# schematic.net
KiCad netlist of a schematic drawn in Altium Designer
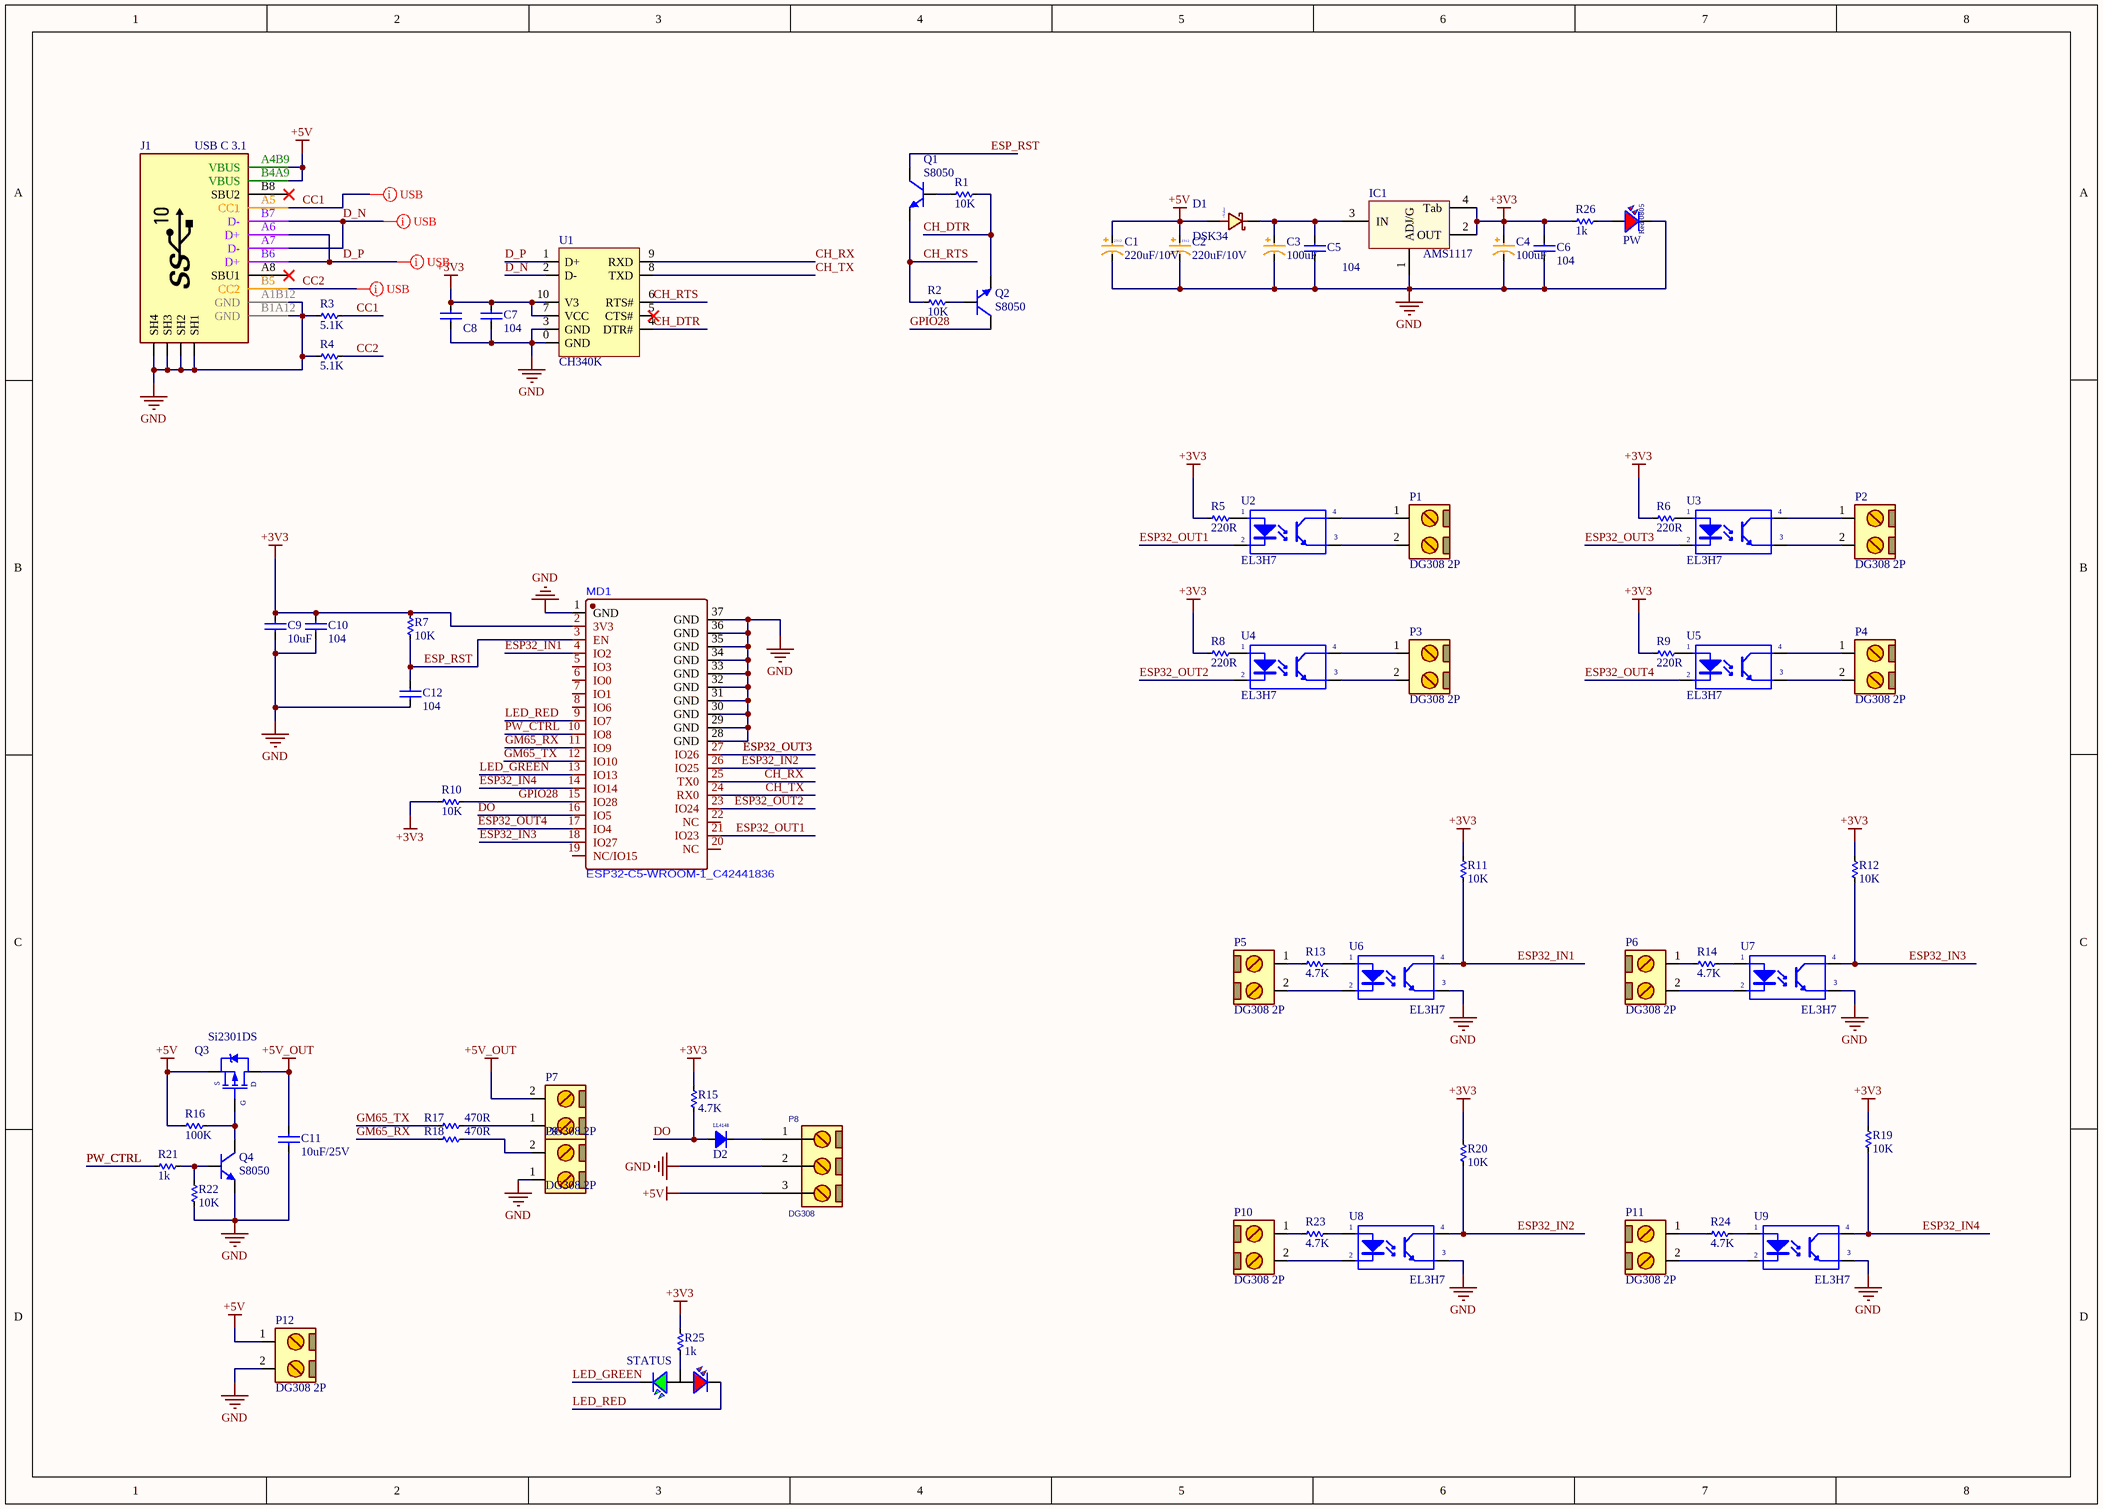
[diagram p0: schematic.SchDoc]

(export (version "E")
  (design (tool "Eeschema 10.0.6"))
  (components
    (comp (ref "C1")
      (value "220uF/10V")
      (footprint "C_tantalum_6032-2312")
      (description "Cap SMD 2312 (6032)")
      (libsource (lib "RD Integrated_Library") (part "Cap Tantalum 220uF 10V 2312"))
    )
    (comp (ref "C2")
      (value "220uF/10V")
      (footprint "C_tantalum_6032-2312")
      (description "Cap SMD 2312 (6032)")
      (libsource (lib "RD Integrated_Library") (part "Cap Tantalum 220uF 10V 2312"))
    )
    (comp (ref "C3")
      (value "100uF")
      (footprint "C_TANTALUM_3528_1210")
      (description "Cap Tantalum SMD 1210 (3528)")
      (fields (field (name "DESIGNED BY") "TranLuyen"))
      (libsource (lib "RD Integrated_Library") (part "Cap Tantalum 100uF 10V 1210 (3528)"))
    )
    (comp (ref "C4")
      (value "100uF")
      (footprint "C_TANTALUM_3528_1210")
      (description "Cap Tantalum SMD 1210 (3528)")
      (fields (field (name "DESIGNED BY") "TranLuyen"))
      (libsource (lib "RD Integrated_Library") (part "Cap Tantalum 100uF 10V 1210 (3528)"))
    )
    (comp (ref "C5")
      (value "104")
      (footprint "C_0805_SMD")
      (description "Cap SMD 0805 104-100nF-0.1uF 50V")
      (libsource (lib "RD Integrated_Library") (part "Cap 0805 104 100nF"))
    )
    (comp (ref "C6")
      (value "104")
      (footprint "C_0805_SMD")
      (description "Cap SMD 0805 104-100nF-0.1uF 50V")
      (libsource (lib "RD Integrated_Library") (part "Cap 0805 104 100nF"))
    )
    (comp (ref "C7")
      (value "104")
      (footprint "C_0805_SMD")
      (description "Cap SMD 0805 104-100nF-0.1uF 50V")
      (libsource (lib "RD Integrated_Library") (part "Cap 0805 104 100nF"))
    )
    (comp (ref "C8")
      (value "10uF/25V")
      (footprint "C_0805_SMD")
      (description "Cap SMD 0805 10uF")
      (libsource (lib "RD Integrated_Library") (part "Cap 0805 10uF 25V"))
    )
    (comp (ref "C9")
      (value "10uF")
      (footprint "C1206")
      (description "Cap SMD 1206 105-10uF 50V")
      (libsource (lib "RD Integrated_Library") (part "Cap 1206 10uF 50V"))
    )
    (comp (ref "C10")
      (value "104")
      (footprint "C_0805_SMD")
      (description "Cap SMD 0805 104-100nF-0.1uF 50V")
      (libsource (lib "RD Integrated_Library") (part "Cap 0805 104 100nF"))
    )
    (comp (ref "C11")
      (value "10uF/25V")
      (footprint "C_0805_SMD")
      (description "Cap SMD 0805 10uF")
      (libsource (lib "RD Integrated_Library") (part "Cap 0805 10uF 25V"))
    )
    (comp (ref "C12")
      (value "104")
      (footprint "C_0805_SMD")
      (description "Cap SMD 0805 104-100nF-0.1uF 50V")
      (libsource (lib "RD Integrated_Library") (part "Cap 0805 104 100nF"))
    )
    (comp (ref "D1")
      (value "DSK34")
      (footprint "D_SOD123W")
      (description "Surface-Mount Schottky Barrier Rectifier")
      (libsource (lib "RD Integrated_Library") (part "DSK34-SOD-123"))
    )
    (comp (ref "D2")
      (value "LL4148")
      (footprint "SOD80C_MFG")
      (description "0.2A, 100V, SOD80")
      (fields (field (name "DESIGNED BY") "Nhox"))
      (libsource (lib "RD Integrated_Library") (part "LL4148"))
    )
    (comp (ref "IC1")
      (value "AMS1117")
      (footprint "SOT223-4N")
      (description "SOT-223")
      (libsource (lib "RD Integrated_Library") (part "AMS1117-3.3V SOT223"))
    )
    (comp (ref "J1")
      (value "USB C 3.1")
      (footprint "USBC_SMD_16_USB4105 PAD L")
      (description "CONN, USB, Type C, USB 2.0, Right-Angle, SMD")
      (libsource (lib "RD Integrated_Library") (part "CONN_USBC_SMD_16_USB4105"))
    )
    (comp (ref "MD1")
      (value "ESP32-C5-WROOM-1_C42441836")
      (footprint "COMM-SMD_37P-P1.27-L27.5-W18.0-ESP32-C5-WROOM-1")
      (libsource (lib "CuongRD") (part "ESP32-C5-WROOM-1_C42441836"))
    )
    (comp (ref "P1")
      (value "DG308 2P")
      (footprint "DG308 KF120 2.54mm 2P - duplicate")
      (description "Header, 2-Pin, Medium DG308-KF120 2.54 2P 2.54mm")
      (fields (field (name "DESIGNED BY") "TranLuyen"))
      (libsource (lib "Schlib1") (part "DG308-KF120-2.54 2P-2.54mm"))
    )
    (comp (ref "P2")
      (value "DG308 2P")
      (footprint "DG308 KF120 2.54mm 2P - duplicate")
      (description "Header, 2-Pin, Medium DG308-KF120 2.54 2P 2.54mm")
      (fields (field (name "DESIGNED BY") "TranLuyen"))
      (libsource (lib "Schlib1") (part "DG308-KF120-2.54 2P-2.54mm"))
    )
    (comp (ref "P3")
      (value "DG308 2P")
      (footprint "DG308 KF120 2.54mm 2P - duplicate")
      (description "Header, 2-Pin, Medium DG308-KF120 2.54 2P 2.54mm")
      (fields (field (name "DESIGNED BY") "TranLuyen"))
      (libsource (lib "Schlib1") (part "DG308-KF120-2.54 2P-2.54mm"))
    )
    (comp (ref "P4")
      (value "DG308 2P")
      (footprint "DG308 KF120 2.54mm 2P - duplicate")
      (description "Header, 2-Pin, Medium DG308-KF120 2.54 2P 2.54mm")
      (fields (field (name "DESIGNED BY") "TranLuyen"))
      (libsource (lib "Schlib1") (part "DG308-KF120-2.54 2P-2.54mm"))
    )
    (comp (ref "P5")
      (value "DG308 2P")
      (footprint "DG308 KF120 2.54mm 2P - duplicate")
      (description "Header, 2-Pin, Medium DG308-KF120 2.54 2P 2.54mm")
      (fields (field (name "DESIGNED BY") "TranLuyen"))
      (libsource (lib "") (part "DG308-KF120-2.54 2P-2.54mm_1"))
    )
    (comp (ref "P6")
      (value "DG308 2P")
      (footprint "DG308 KF120 2.54mm 2P - duplicate")
      (description "Header, 2-Pin, Medium DG308-KF120 2.54 2P 2.54mm")
      (fields (field (name "DESIGNED BY") "TranLuyen"))
      (libsource (lib "") (part "DG308-KF120-2.54 2P-2.54mm_1"))
    )
    (comp (ref "P7")
      (value "DG308 2P")
      (footprint "DG308 KF120 2.54mm 2P - duplicate")
      (description "Header, 2-Pin, Medium DG308-KF120 2.54 2P 2.54mm")
      (fields (field (name "DESIGNED BY") "TranLuyen"))
      (libsource (lib "") (part "DG308-KF120-2.54 2P-2.54mm_2"))
    )
    (comp (ref "P8")
      (value "DG308")
      (footprint "DG308 KF120 2.54mm 3P")
      (description "Header, 2-Pin, Medium DG308-KF120 2.54 3P 2.54mm")
      (fields (field (name "DESIGNED BY") "TranLuyen"))
      (libsource (lib "Schlib1") (part "DG308-KF120-2.54 3P-2.54mm"))
    )
    (comp (ref "P9")
      (value "DG308 2P")
      (footprint "DG308 KF120 2.54mm 2P - duplicate")
      (description "Header, 2-Pin, Medium DG308-KF120 2.54 2P 2.54mm")
      (fields (field (name "DESIGNED BY") "TranLuyen"))
      (libsource (lib "") (part "DG308-KF120-2.54 2P-2.54mm_2"))
    )
    (comp (ref "P10")
      (value "DG308 2P")
      (footprint "DG308 KF120 2.54mm 2P - duplicate")
      (description "Header, 2-Pin, Medium DG308-KF120 2.54 2P 2.54mm")
      (fields (field (name "DESIGNED BY") "TranLuyen"))
      (libsource (lib "") (part "DG308-KF120-2.54 2P-2.54mm_1"))
    )
    (comp (ref "P11")
      (value "DG308 2P")
      (footprint "DG308 KF120 2.54mm 2P - duplicate")
      (description "Header, 2-Pin, Medium DG308-KF120 2.54 2P 2.54mm")
      (fields (field (name "DESIGNED BY") "TranLuyen"))
      (libsource (lib "") (part "DG308-KF120-2.54 2P-2.54mm_1"))
    )
    (comp (ref "P12")
      (value "DG308 2P")
      (footprint "DG308 KF120 2.54mm 2P - duplicate")
      (description "Header, 2-Pin, Medium DG308-KF120 2.54 2P 2.54mm")
      (fields (field (name "DESIGNED BY") "TranLuyen"))
      (libsource (lib "Schlib1") (part "DG308-KF120-2.54 2P-2.54mm"))
    )
    (comp (ref "PW")
      (value "LED RED")
      (footprint "LED 0805 Red")
      (description "LED 0805 SMD RED")
      (fields (field (name "DESIGNED BY") "TranLuyen"))
      (libsource (lib "RD Integrated_Library") (part "LED 0805 RED"))
    )
    (comp (ref "Q1")
      (value "S8050")
      (footprint "SOT23_N NXP")
      (description "J3Y-NPN SMD Transistor SOT23")
      (libsource (lib "RD Integrated_Library") (part "S8050 SOT-23"))
    )
    (comp (ref "Q2")
      (value "S8050")
      (footprint "SOT23_N NXP")
      (description "J3Y-NPN SMD Transistor SOT23")
      (libsource (lib "RD Integrated_Library") (part "S8050 SOT-23"))
    )
    (comp (ref "Q3")
      (value "Si2301DS")
      (footprint "SOT23_N NXP")
      (description "P-Channel 1.25W, Vds = -20V, Vgs = +-8V, Vgs -4.5V Id = -2.3A, Vgs -2.5V Id = -1.9A")
      (libsource (lib "RD Integrated_Library") (part "Si2301DS"))
    )
    (comp (ref "Q4")
      (value "S8050")
      (footprint "SOT23_N NXP")
      (description "J3Y-NPN SMD Transistor SOT23")
      (libsource (lib "RD Integrated_Library") (part "S8050 SOT-23"))
    )
    (comp (ref "R1")
      (value "10K")
      (footprint "RES-SMD-0805")
      (description "Resistor SMD 0805")
      (libsource (lib "RD Integrated_Library") (part "Res 10k 0805"))
    )
    (comp (ref "R2")
      (value "10K")
      (footprint "RES-SMD-0805")
      (description "Resistor SMD 0805")
      (libsource (lib "RD Integrated_Library") (part "Res 10k 0805"))
    )
    (comp (ref "R3")
      (value "5.1K")
      (footprint "RES-SMD-0805")
      (description "Resistor SMD 0805")
      (libsource (lib "RD Integrated_Library") (part "Res 5.1k 0805"))
    )
    (comp (ref "R4")
      (value "5.1K")
      (footprint "RES-SMD-0805")
      (description "Resistor SMD 0805")
      (libsource (lib "RD Integrated_Library") (part "Res 5.1k 0805"))
    )
    (comp (ref "R5")
      (value "220R")
      (footprint "RES-SMD-0805")
      (description "Resistor SMD 0805")
      (libsource (lib "RD Integrated_Library") (part "Res 220R 0805"))
    )
    (comp (ref "R6")
      (value "220R")
      (footprint "RES-SMD-0805")
      (description "Resistor SMD 0805")
      (libsource (lib "RD Integrated_Library") (part "Res 220R 0805"))
    )
    (comp (ref "R7")
      (value "10K")
      (footprint "RES-SMD-0805")
      (description "Resistor SMD 0805")
      (libsource (lib "RD Integrated_Library") (part "Res 10k 0805"))
    )
    (comp (ref "R8")
      (value "220R")
      (footprint "RES-SMD-0805")
      (description "Resistor SMD 0805")
      (libsource (lib "RD Integrated_Library") (part "Res 220R 0805"))
    )
    (comp (ref "R9")
      (value "220R")
      (footprint "RES-SMD-0805")
      (description "Resistor SMD 0805")
      (libsource (lib "RD Integrated_Library") (part "Res 220R 0805"))
    )
    (comp (ref "R10")
      (value "10K")
      (footprint "RES-SMD-0805")
      (description "Resistor SMD 0805")
      (libsource (lib "RD Integrated_Library") (part "Res 10k 0805"))
    )
    (comp (ref "R11")
      (value "10K")
      (footprint "RES-SMD-0805")
      (description "Resistor SMD 0805")
      (libsource (lib "RD Integrated_Library") (part "Res 10k 0805"))
    )
    (comp (ref "R12")
      (value "10K")
      (footprint "RES-SMD-0805")
      (description "Resistor SMD 0805")
      (libsource (lib "RD Integrated_Library") (part "Res 10k 0805"))
    )
    (comp (ref "R13")
      (value "4.7K")
      (footprint "RES-SMD-1206")
      (description "Resistor SMD 1206")
      (libsource (lib "Resistor") (part "Res 4.7K 1206"))
    )
    (comp (ref "R14")
      (value "4.7K")
      (footprint "RES-SMD-1206")
      (description "Resistor SMD 1206")
      (libsource (lib "Resistor") (part "Res 4.7K 1206"))
    )
    (comp (ref "R15")
      (value "4.7K")
      (footprint "RES-SMD-0805")
      (description "Resistor SMD 0805")
      (libsource (lib "RD Integrated_Library") (part "Res 4.7k 0805"))
    )
    (comp (ref "R16")
      (value "100K")
      (footprint "RES-SMD-0805")
      (description "Resistor SMD 0805")
      (libsource (lib "RD Integrated_Library") (part "Res 100k 0805"))
    )
    (comp (ref "R17")
      (value "470R")
      (footprint "RES-SMD-0805")
      (description "Resistor SMD 0805")
      (libsource (lib "RD Integrated_Library") (part "Res 470R 0805"))
    )
    (comp (ref "R18")
      (value "470R")
      (footprint "RES-SMD-0805")
      (description "Resistor SMD 0805")
      (libsource (lib "RD Integrated_Library") (part "Res 470R 0805"))
    )
    (comp (ref "R19")
      (value "10K")
      (footprint "RES-SMD-0805")
      (description "Resistor SMD 0805")
      (libsource (lib "RD Integrated_Library") (part "Res 10k 0805"))
    )
    (comp (ref "R20")
      (value "10K")
      (footprint "RES-SMD-0805")
      (description "Resistor SMD 0805")
      (libsource (lib "RD Integrated_Library") (part "Res 10k 0805"))
    )
    (comp (ref "R21")
      (value "1k")
      (footprint "RES-SMD-0805")
      (description "Resistor SMD 0805")
      (libsource (lib "RD Integrated_Library") (part "Res 1k 0805"))
    )
    (comp (ref "R22")
      (value "10K")
      (footprint "RES-SMD-0805")
      (description "Resistor SMD 0805")
      (libsource (lib "RD Integrated_Library") (part "Res 10k 0805"))
    )
    (comp (ref "R23")
      (value "4.7K")
      (footprint "RES-SMD-1206")
      (description "Resistor SMD 1206")
      (libsource (lib "Resistor") (part "Res 4.7K 1206"))
    )
    (comp (ref "R24")
      (value "4.7K")
      (footprint "RES-SMD-1206")
      (description "Resistor SMD 1206")
      (libsource (lib "Resistor") (part "Res 4.7K 1206"))
    )
    (comp (ref "R25")
      (value "1k")
      (footprint "RES-SMD-0805")
      (description "Resistor SMD 0805")
      (libsource (lib "RD Integrated_Library") (part "Res 1k 0805"))
    )
    (comp (ref "R26")
      (value "1k")
      (footprint "RES-SMD-0805")
      (description "Resistor SMD 0805")
      (libsource (lib "RD Integrated_Library") (part "Res 1k 0805"))
    )
    (comp (ref "STATUS")
      (value "Led R-G")
      (footprint "Led_3mm_3_Pin_CA")
      (description "LED 3mm Red Green CA 3 Pin")
      (fields (field (name "DESIGNED BY") "Nhox"))
      (libsource (lib "RD Integrated_Library") (part "LED 3mm Red Green CA 3 Pin"))
    )
    (comp (ref "U1")
      (value "CH340K")
      (footprint "SSOP10 / ESSOP-10")
      (description "USB To Serial")
      (fields (field (name "DESIGNED BY") "Nhox"))
      (libsource (lib "RD Integrated_Library") (part "CH340K"))
    )
    (comp (ref "U2")
      (value "EL3H7")
      (footprint "SO_4-EL3H7-G_MFG")
      (description "Optocoupler DC-IN 1-CH Transistor DC-OUT 4-Pin SSOP T/R")
      (fields (field (name "DESIGNED BY") "TranLuyen"))
      (libsource (lib "RD Integrated_Library") (part "EL3H7(C)(TA)-VG SSOP-4"))
    )
    (comp (ref "U3")
      (value "EL3H7")
      (footprint "SO_4-EL3H7-G_MFG")
      (description "Optocoupler DC-IN 1-CH Transistor DC-OUT 4-Pin SSOP T/R")
      (fields (field (name "DESIGNED BY") "TranLuyen"))
      (libsource (lib "RD Integrated_Library") (part "EL3H7(C)(TA)-VG SSOP-4"))
    )
    (comp (ref "U4")
      (value "EL3H7")
      (footprint "SO_4-EL3H7-G_MFG")
      (description "Optocoupler DC-IN 1-CH Transistor DC-OUT 4-Pin SSOP T/R")
      (fields (field (name "DESIGNED BY") "TranLuyen"))
      (libsource (lib "RD Integrated_Library") (part "EL3H7(C)(TA)-VG SSOP-4"))
    )
    (comp (ref "U5")
      (value "EL3H7")
      (footprint "SO_4-EL3H7-G_MFG")
      (description "Optocoupler DC-IN 1-CH Transistor DC-OUT 4-Pin SSOP T/R")
      (fields (field (name "DESIGNED BY") "TranLuyen"))
      (libsource (lib "RD Integrated_Library") (part "EL3H7(C)(TA)-VG SSOP-4"))
    )
    (comp (ref "U6")
      (value "EL3H7")
      (footprint "SO_4-EL3H7-G_MFG")
      (description "Optocoupler DC-IN 1-CH Transistor DC-OUT 4-Pin SSOP T/R")
      (fields (field (name "DESIGNED BY") "TranLuyen"))
      (libsource (lib "RD Integrated_Library") (part "EL3H7(C)(TA)-VG SSOP-4"))
    )
    (comp (ref "U7")
      (value "EL3H7")
      (footprint "SO_4-EL3H7-G_MFG")
      (description "Optocoupler DC-IN 1-CH Transistor DC-OUT 4-Pin SSOP T/R")
      (fields (field (name "DESIGNED BY") "TranLuyen"))
      (libsource (lib "RD Integrated_Library") (part "EL3H7(C)(TA)-VG SSOP-4"))
    )
    (comp (ref "U8")
      (value "EL3H7")
      (footprint "SO_4-EL3H7-G_MFG")
      (description "Optocoupler DC-IN 1-CH Transistor DC-OUT 4-Pin SSOP T/R")
      (fields (field (name "DESIGNED BY") "TranLuyen"))
      (libsource (lib "RD Integrated_Library") (part "EL3H7(C)(TA)-VG SSOP-4"))
    )
    (comp (ref "U9")
      (value "EL3H7")
      (footprint "SO_4-EL3H7-G_MFG")
      (description "Optocoupler DC-IN 1-CH Transistor DC-OUT 4-Pin SSOP T/R")
      (fields (field (name "DESIGNED BY") "TranLuyen"))
      (libsource (lib "RD Integrated_Library") (part "EL3H7(C)(TA)-VG SSOP-4"))
    )
  )
  (nets
    (net (code "1") (name "+3V3") (class "Default")
      (node (ref "C10") (pin "2") (pinfunction "2_2") (pintype "passive"))
      (node (ref "C4") (pin "1") (pinfunction "1_1") (pintype "passive"))
      (node (ref "C6") (pin "2") (pinfunction "2_2") (pintype "passive"))
      (node (ref "C7") (pin "2") (pinfunction "2_2") (pintype "passive"))
      (node (ref "C8") (pin "2") (pinfunction "2_2") (pintype "passive"))
      (node (ref "C9") (pin "2") (pinfunction "2_2") (pintype "passive"))
      (node (ref "IC1") (pin "2") (pinfunction "OUT_2") (pintype "passive"))
      (node (ref "IC1") (pin "4") (pinfunction "Tab_4") (pintype "passive"))
      (node (ref "MD1") (pin "2") (pinfunction "3V3_2") (pintype "passive"))
      (node (ref "R10") (pin "1") (pinfunction "1_1") (pintype "passive"))
      (node (ref "R11") (pin "1") (pinfunction "1_1") (pintype "passive"))
      (node (ref "R12") (pin "1") (pinfunction "1_1") (pintype "passive"))
      (node (ref "R15") (pin "1") (pinfunction "1_1") (pintype "passive"))
      (node (ref "R19") (pin "1") (pinfunction "1_1") (pintype "passive"))
      (node (ref "R20") (pin "1") (pinfunction "1_1") (pintype "passive"))
      (node (ref "R25") (pin "1") (pinfunction "1_1") (pintype "passive"))
      (node (ref "R26") (pin "1") (pinfunction "1_1") (pintype "passive"))
      (node (ref "R5") (pin "2") (pinfunction "2_2") (pintype "passive"))
      (node (ref "R6") (pin "2") (pinfunction "2_2") (pintype "passive"))
      (node (ref "R7") (pin "1") (pinfunction "1_1") (pintype "passive"))
      (node (ref "R8") (pin "2") (pinfunction "2_2") (pintype "passive"))
      (node (ref "R9") (pin "2") (pinfunction "2_2") (pintype "passive"))
      (node (ref "U1") (pin "10") (pinfunction "V3_10") (pintype "passive"))
      (node (ref "U1") (pin "7") (pinfunction "VCC_7") (pintype "passive"))
    )
    (net (code "2") (name "+5V") (class "Default")
      (node (ref "C1") (pin "1") (pinfunction "1_1") (pintype "passive"))
      (node (ref "C2") (pin "1") (pinfunction "1_1") (pintype "passive"))
      (node (ref "D1") (pin "1") (pinfunction "A_1") (pintype "passive"))
      (node (ref "J1") (pin "A4B9") (pinfunction "VBUS_A4B9") (pintype "passive"))
      (node (ref "J1") (pin "B4A9") (pinfunction "VBUS_B4A9") (pintype "passive"))
      (node (ref "P12") (pin "1") (pinfunction "1_1") (pintype "passive"))
      (node (ref "P8") (pin "3") (pinfunction "3_3") (pintype "passive"))
      (node (ref "Q3") (pin "2") (pinfunction "S_2") (pintype "passive"))
      (node (ref "R16") (pin "1") (pinfunction "1_1") (pintype "passive"))
    )
    (net (code "3") (name "+5V_OUT") (class "Default")
      (node (ref "C11") (pin "2") (pinfunction "2_2") (pintype "passive"))
      (node (ref "P7") (pin "2") (pinfunction "2_2") (pintype "passive"))
      (node (ref "Q3") (pin "3") (pinfunction "D_3") (pintype "passive"))
    )
    (net (code "4") (name "/CC1") (class "Default")
      (node (ref "J1") (pin "A5") (pinfunction "CC1_A5") (pintype "passive"))
      (node (ref "R3") (pin "1") (pinfunction "1_1") (pintype "passive"))
    )
    (net (code "5") (name "/CC2") (class "Default")
      (node (ref "J1") (pin "B5") (pinfunction "CC2_B5") (pintype "passive"))
      (node (ref "R4") (pin "1") (pinfunction "1_1") (pintype "passive"))
    )
    (net (code "6") (name "/CH_DTR") (class "Default")
      (node (ref "Q2") (pin "2") (pinfunction "E_2") (pintype "passive"))
      (node (ref "R1") (pin "1") (pinfunction "1_1") (pintype "passive"))
      (node (ref "U1") (pin "4") (pinfunction "DTR#_4") (pintype "passive"))
    )
    (net (code "7") (name "/CH_RTS") (class "Default")
      (node (ref "Q1") (pin "2") (pinfunction "E_2") (pintype "passive"))
      (node (ref "R2") (pin "2") (pinfunction "2_2") (pintype "passive"))
      (node (ref "U1") (pin "6") (pinfunction "RTS#_6") (pintype "passive"))
    )
    (net (code "8") (name "/CH_RX") (class "Default")
      (node (ref "MD1") (pin "25") (pinfunction "TX0_25") (pintype "passive"))
      (node (ref "U1") (pin "9") (pinfunction "RXD_9") (pintype "passive"))
    )
    (net (code "9") (name "/CH_TX") (class "Default")
      (node (ref "MD1") (pin "24") (pinfunction "RX0_24") (pintype "passive"))
      (node (ref "U1") (pin "8") (pinfunction "TXD_8") (pintype "passive"))
    )
    (net (code "10") (name "/DO") (class "Default")
      (node (ref "D2") (pin "2") (pinfunction "2_2") (pintype "passive"))
      (node (ref "MD1") (pin "16") (pinfunction "IO5_16") (pintype "passive"))
      (node (ref "R15") (pin "2") (pinfunction "2_2") (pintype "passive"))
    )
    (net (code "11") (name "/D_N") (class "Default")
      (node (ref "J1") (pin "A7") (pinfunction "D-_A7") (pintype "passive"))
      (node (ref "J1") (pin "B7") (pinfunction "D-_B7") (pintype "passive"))
      (node (ref "U1") (pin "2") (pinfunction "D-_2") (pintype "passive"))
    )
    (net (code "12") (name "/D_P") (class "Default")
      (node (ref "J1") (pin "A6") (pinfunction "D+_A6") (pintype "passive"))
      (node (ref "J1") (pin "B6") (pinfunction "D+_B6") (pintype "passive"))
      (node (ref "U1") (pin "1") (pinfunction "D+_1") (pintype "passive"))
    )
    (net (code "13") (name "/ESP32_IN1") (class "Default")
      (node (ref "MD1") (pin "4") (pinfunction "IO2_4") (pintype "passive"))
      (node (ref "R11") (pin "2") (pinfunction "2_2") (pintype "passive"))
      (node (ref "U6") (pin "4") (pinfunction "C_4") (pintype "passive"))
    )
    (net (code "14") (name "/ESP32_IN2") (class "Default")
      (node (ref "MD1") (pin "26") (pinfunction "IO25_26") (pintype "passive"))
      (node (ref "R20") (pin "2") (pinfunction "2_2") (pintype "passive"))
      (node (ref "U8") (pin "4") (pinfunction "C_4") (pintype "passive"))
    )
    (net (code "15") (name "/ESP32_IN3") (class "Default")
      (node (ref "MD1") (pin "18") (pinfunction "IO27_18") (pintype "passive"))
      (node (ref "R12") (pin "2") (pinfunction "2_2") (pintype "passive"))
      (node (ref "U7") (pin "4") (pinfunction "C_4") (pintype "passive"))
    )
    (net (code "16") (name "/ESP32_IN4") (class "Default")
      (node (ref "MD1") (pin "14") (pinfunction "IO14_14") (pintype "passive"))
      (node (ref "R19") (pin "2") (pinfunction "2_2") (pintype "passive"))
      (node (ref "U9") (pin "4") (pinfunction "C_4") (pintype "passive"))
    )
    (net (code "17") (name "/ESP32_OUT1") (class "Default")
      (node (ref "MD1") (pin "21") (pinfunction "IO23_21") (pintype "passive"))
      (node (ref "U2") (pin "2") (pinfunction "K_2") (pintype "passive"))
    )
    (net (code "18") (name "/ESP32_OUT2") (class "Default")
      (node (ref "MD1") (pin "23") (pinfunction "IO24_23") (pintype "passive"))
      (node (ref "U4") (pin "2") (pinfunction "K_2") (pintype "passive"))
    )
    (net (code "19") (name "/ESP32_OUT3") (class "Default")
      (node (ref "MD1") (pin "27") (pinfunction "IO26_27") (pintype "passive"))
      (node (ref "U3") (pin "2") (pinfunction "K_2") (pintype "passive"))
    )
    (net (code "20") (name "/ESP32_OUT4") (class "Default")
      (node (ref "MD1") (pin "17") (pinfunction "IO4_17") (pintype "passive"))
      (node (ref "U5") (pin "2") (pinfunction "K_2") (pintype "passive"))
    )
    (net (code "21") (name "/ESP_RST") (class "Default")
      (node (ref "C12") (pin "2") (pinfunction "2_2") (pintype "passive"))
      (node (ref "MD1") (pin "3") (pinfunction "EN_3") (pintype "passive"))
      (node (ref "Q1") (pin "3") (pinfunction "C_3") (pintype "passive"))
      (node (ref "R7") (pin "2") (pinfunction "2_2") (pintype "passive"))
    )
    (net (code "22") (name "/GM65_RX") (class "Default")
      (node (ref "MD1") (pin "11") (pinfunction "IO9_11") (pintype "passive"))
      (node (ref "R18") (pin "2") (pinfunction "2_2") (pintype "passive"))
    )
    (net (code "23") (name "/GM65_TX") (class "Default")
      (node (ref "MD1") (pin "12") (pinfunction "IO10_12") (pintype "passive"))
      (node (ref "R17") (pin "2") (pinfunction "2_2") (pintype "passive"))
    )
    (net (code "24") (name "/GPIO28") (class "Default")
      (node (ref "MD1") (pin "15") (pinfunction "IO28_15") (pintype "passive"))
      (node (ref "Q2") (pin "3") (pinfunction "C_3") (pintype "passive"))
      (node (ref "R10") (pin "2") (pinfunction "2_2") (pintype "passive"))
    )
    (net (code "25") (name "/LED_GREEN") (class "Default")
      (node (ref "MD1") (pin "13") (pinfunction "IO13_13") (pintype "passive"))
      (node (ref "STATUS") (pin "3") (pinfunction "3_3") (pintype "passive"))
    )
    (net (code "26") (name "/LED_RED") (class "Default")
      (node (ref "MD1") (pin "9") (pinfunction "IO7_9") (pintype "passive"))
      (node (ref "STATUS") (pin "1") (pinfunction "1_1") (pintype "passive"))
    )
    (net (code "27") (name "/PW_CTRL") (class "Default")
      (node (ref "MD1") (pin "10") (pinfunction "IO8_10") (pintype "passive"))
      (node (ref "R21") (pin "2") (pinfunction "2_2") (pintype "passive"))
    )
    (net (code "28") (name "GND") (class "Default")
      (node (ref "C1") (pin "2") (pinfunction "2_2") (pintype "passive"))
      (node (ref "C10") (pin "1") (pinfunction "1_1") (pintype "passive"))
      (node (ref "C11") (pin "1") (pinfunction "1_1") (pintype "passive"))
      (node (ref "C12") (pin "1") (pinfunction "1_1") (pintype "passive"))
      (node (ref "C2") (pin "2") (pinfunction "2_2") (pintype "passive"))
      (node (ref "C3") (pin "2") (pinfunction "2_2") (pintype "passive"))
      (node (ref "C4") (pin "2") (pinfunction "2_2") (pintype "passive"))
      (node (ref "C5") (pin "1") (pinfunction "1_1") (pintype "passive"))
      (node (ref "C6") (pin "1") (pinfunction "1_1") (pintype "passive"))
      (node (ref "C7") (pin "1") (pinfunction "1_1") (pintype "passive"))
      (node (ref "C8") (pin "1") (pinfunction "1_1") (pintype "passive"))
      (node (ref "C9") (pin "1") (pinfunction "1_1") (pintype "passive"))
      (node (ref "IC1") (pin "1") (pinfunction "ADJ/G_1") (pintype "passive"))
      (node (ref "J1") (pin "A1B12") (pinfunction "GND_A1B12") (pintype "passive"))
      (node (ref "J1") (pin "B1A12") (pinfunction "GND_B1A12") (pintype "passive"))
      (node (ref "J1") (pin "SH1") (pinfunction "SH1_SH1") (pintype "passive"))
      (node (ref "J1") (pin "SH2") (pinfunction "SH2_SH2") (pintype "passive"))
      (node (ref "J1") (pin "SH3") (pinfunction "SH3_SH3") (pintype "passive"))
      (node (ref "J1") (pin "SH4") (pinfunction "SH4_SH4") (pintype "passive"))
      (node (ref "MD1") (pin "1") (pinfunction "GND_1") (pintype "passive"))
      (node (ref "MD1") (pin "28") (pinfunction "GND_28") (pintype "passive"))
      (node (ref "MD1") (pin "29") (pinfunction "GND_29") (pintype "passive"))
      (node (ref "MD1") (pin "30") (pinfunction "GND_30") (pintype "passive"))
      (node (ref "MD1") (pin "31") (pinfunction "GND_31") (pintype "passive"))
      (node (ref "MD1") (pin "32") (pinfunction "GND_32") (pintype "passive"))
      (node (ref "MD1") (pin "33") (pinfunction "GND_33") (pintype "passive"))
      (node (ref "MD1") (pin "34") (pinfunction "GND_34") (pintype "passive"))
      (node (ref "MD1") (pin "35") (pinfunction "GND_35") (pintype "passive"))
      (node (ref "MD1") (pin "36") (pinfunction "GND_36") (pintype "passive"))
      (node (ref "MD1") (pin "37") (pinfunction "GND_37") (pintype "passive"))
      (node (ref "P12") (pin "2") (pinfunction "2_2") (pintype "passive"))
      (node (ref "P8") (pin "2") (pinfunction "2_2") (pintype "passive"))
      (node (ref "P9") (pin "1") (pinfunction "1_1") (pintype "passive"))
      (node (ref "PW") (pin "2") (pinfunction "2_2") (pintype "passive"))
      (node (ref "Q4") (pin "2") (pinfunction "E_2") (pintype "passive"))
      (node (ref "R22") (pin "2") (pinfunction "2_2") (pintype "passive"))
      (node (ref "R3") (pin "2") (pinfunction "2_2") (pintype "passive"))
      (node (ref "R4") (pin "2") (pinfunction "2_2") (pintype "passive"))
      (node (ref "U1") (pin "0") (pinfunction "GND_0") (pintype "passive"))
      (node (ref "U1") (pin "3") (pinfunction "GND_3") (pintype "passive"))
      (node (ref "U6") (pin "3") (pinfunction "E_3") (pintype "passive"))
      (node (ref "U7") (pin "3") (pinfunction "E_3") (pintype "passive"))
      (node (ref "U8") (pin "3") (pinfunction "E_3") (pintype "passive"))
      (node (ref "U9") (pin "3") (pinfunction "E_3") (pintype "passive"))
    )
    (net (code "29") (name "Net-(D1-K)") (class "Default")
      (node (ref "C3") (pin "1") (pinfunction "1_1") (pintype "passive"))
      (node (ref "C5") (pin "2") (pinfunction "2_2") (pintype "passive"))
      (node (ref "D1") (pin "2") (pinfunction "K_2") (pintype "passive"))
      (node (ref "IC1") (pin "3") (pinfunction "IN_3") (pintype "passive"))
    )
    (net (code "30") (name "Net-(D2-Pad1)") (class "Default")
      (node (ref "D2") (pin "1") (pinfunction "1_1") (pintype "passive"))
      (node (ref "P8") (pin "1") (pinfunction "1_1") (pintype "passive"))
    )
    (net (code "31") (name "Net-(P5-Pad1)") (class "Default")
      (node (ref "P5") (pin "1") (pinfunction "1_1") (pintype "passive"))
      (node (ref "R13") (pin "1") (pinfunction "1_1") (pintype "passive"))
    )
    (net (code "32") (name "Net-(P6-Pad1)") (class "Default")
      (node (ref "P6") (pin "1") (pinfunction "1_1") (pintype "passive"))
      (node (ref "R14") (pin "2") (pinfunction "2_2") (pintype "passive"))
    )
    (net (code "33") (name "Net-(P7-Pad1)") (class "Default")
      (node (ref "P7") (pin "1") (pinfunction "1_1") (pintype "passive"))
      (node (ref "R17") (pin "1") (pinfunction "1_1") (pintype "passive"))
    )
    (net (code "34") (name "Net-(P9-Pad2)") (class "Default")
      (node (ref "P9") (pin "2") (pinfunction "2_2") (pintype "passive"))
      (node (ref "R18") (pin "1") (pinfunction "1_1") (pintype "passive"))
    )
    (net (code "35") (name "Net-(P10-Pad1)") (class "Default")
      (node (ref "P10") (pin "1") (pinfunction "1_1") (pintype "passive"))
      (node (ref "R23") (pin "1") (pinfunction "1_1") (pintype "passive"))
    )
    (net (code "36") (name "Net-(P11-Pad1)") (class "Default")
      (node (ref "P11") (pin "1") (pinfunction "1_1") (pintype "passive"))
      (node (ref "R24") (pin "2") (pinfunction "2_2") (pintype "passive"))
    )
    (net (code "37") (name "Net-(PW-Pad1)") (class "Default")
      (node (ref "PW") (pin "1") (pinfunction "1_1") (pintype "passive"))
      (node (ref "R26") (pin "2") (pinfunction "2_2") (pintype "passive"))
    )
    (net (code "38") (name "Net-(Q1-B)") (class "Default")
      (node (ref "Q1") (pin "1") (pinfunction "B_1") (pintype "passive"))
      (node (ref "R1") (pin "2") (pinfunction "2_2") (pintype "passive"))
    )
    (net (code "39") (name "Net-(Q2-B)") (class "Default")
      (node (ref "Q2") (pin "1") (pinfunction "B_1") (pintype "passive"))
      (node (ref "R2") (pin "1") (pinfunction "1_1") (pintype "passive"))
    )
    (net (code "40") (name "Net-(Q3-G)") (class "Default")
      (node (ref "Q3") (pin "1") (pinfunction "G_1") (pintype "passive"))
      (node (ref "Q4") (pin "3") (pinfunction "C_3") (pintype "passive"))
      (node (ref "R16") (pin "2") (pinfunction "2_2") (pintype "passive"))
    )
    (net (code "41") (name "Net-(Q4-B)") (class "Default")
      (node (ref "Q4") (pin "1") (pinfunction "B_1") (pintype "passive"))
      (node (ref "R21") (pin "1") (pinfunction "1_1") (pintype "passive"))
      (node (ref "R22") (pin "1") (pinfunction "1_1") (pintype "passive"))
    )
    (net (code "42") (name "Net-(R25-Pad2)") (class "Default")
      (node (ref "R25") (pin "2") (pinfunction "2_2") (pintype "passive"))
      (node (ref "STATUS") (pin "2") (pinfunction "2_2") (pintype "passive"))
    )
    (net (code "43") (name "Net-(U2-A)") (class "Default")
      (node (ref "R5") (pin "1") (pinfunction "1_1") (pintype "passive"))
      (node (ref "U2") (pin "1") (pinfunction "A_1") (pintype "passive"))
    )
    (net (code "44") (name "Net-(U2-C)") (class "Default")
      (node (ref "P1") (pin "1") (pinfunction "1_1") (pintype "passive"))
      (node (ref "U2") (pin "4") (pinfunction "C_4") (pintype "passive"))
    )
    (net (code "45") (name "Net-(U2-E)") (class "Default")
      (node (ref "P1") (pin "2") (pinfunction "2_2") (pintype "passive"))
      (node (ref "U2") (pin "3") (pinfunction "E_3") (pintype "passive"))
    )
    (net (code "46") (name "Net-(U3-A)") (class "Default")
      (node (ref "R6") (pin "1") (pinfunction "1_1") (pintype "passive"))
      (node (ref "U3") (pin "1") (pinfunction "A_1") (pintype "passive"))
    )
    (net (code "47") (name "Net-(U3-C)") (class "Default")
      (node (ref "P2") (pin "1") (pinfunction "1_1") (pintype "passive"))
      (node (ref "U3") (pin "4") (pinfunction "C_4") (pintype "passive"))
    )
    (net (code "48") (name "Net-(U3-E)") (class "Default")
      (node (ref "P2") (pin "2") (pinfunction "2_2") (pintype "passive"))
      (node (ref "U3") (pin "3") (pinfunction "E_3") (pintype "passive"))
    )
    (net (code "49") (name "Net-(U4-A)") (class "Default")
      (node (ref "R8") (pin "1") (pinfunction "1_1") (pintype "passive"))
      (node (ref "U4") (pin "1") (pinfunction "A_1") (pintype "passive"))
    )
    (net (code "50") (name "Net-(U4-C)") (class "Default")
      (node (ref "P3") (pin "1") (pinfunction "1_1") (pintype "passive"))
      (node (ref "U4") (pin "4") (pinfunction "C_4") (pintype "passive"))
    )
    (net (code "51") (name "Net-(U4-E)") (class "Default")
      (node (ref "P3") (pin "2") (pinfunction "2_2") (pintype "passive"))
      (node (ref "U4") (pin "3") (pinfunction "E_3") (pintype "passive"))
    )
    (net (code "52") (name "Net-(U5-A)") (class "Default")
      (node (ref "R9") (pin "1") (pinfunction "1_1") (pintype "passive"))
      (node (ref "U5") (pin "1") (pinfunction "A_1") (pintype "passive"))
    )
    (net (code "53") (name "Net-(U5-C)") (class "Default")
      (node (ref "P4") (pin "1") (pinfunction "1_1") (pintype "passive"))
      (node (ref "U5") (pin "4") (pinfunction "C_4") (pintype "passive"))
    )
    (net (code "54") (name "Net-(U5-E)") (class "Default")
      (node (ref "P4") (pin "2") (pinfunction "2_2") (pintype "passive"))
      (node (ref "U5") (pin "3") (pinfunction "E_3") (pintype "passive"))
    )
    (net (code "55") (name "Net-(U6-A)") (class "Default")
      (node (ref "R13") (pin "2") (pinfunction "2_2") (pintype "passive"))
      (node (ref "U6") (pin "1") (pinfunction "A_1") (pintype "passive"))
    )
    (net (code "56") (name "Net-(U6-K)") (class "Default")
      (node (ref "P5") (pin "2") (pinfunction "2_2") (pintype "passive"))
      (node (ref "U6") (pin "2") (pinfunction "K_2") (pintype "passive"))
    )
    (net (code "57") (name "Net-(U7-A)") (class "Default")
      (node (ref "R14") (pin "1") (pinfunction "1_1") (pintype "passive"))
      (node (ref "U7") (pin "1") (pinfunction "A_1") (pintype "passive"))
    )
    (net (code "58") (name "Net-(U7-K)") (class "Default")
      (node (ref "P6") (pin "2") (pinfunction "2_2") (pintype "passive"))
      (node (ref "U7") (pin "2") (pinfunction "K_2") (pintype "passive"))
    )
    (net (code "59") (name "Net-(U8-A)") (class "Default")
      (node (ref "R23") (pin "2") (pinfunction "2_2") (pintype "passive"))
      (node (ref "U8") (pin "1") (pinfunction "A_1") (pintype "passive"))
    )
    (net (code "60") (name "Net-(U8-K)") (class "Default")
      (node (ref "P10") (pin "2") (pinfunction "2_2") (pintype "passive"))
      (node (ref "U8") (pin "2") (pinfunction "K_2") (pintype "passive"))
    )
    (net (code "61") (name "Net-(U9-A)") (class "Default")
      (node (ref "R24") (pin "1") (pinfunction "1_1") (pintype "passive"))
      (node (ref "U9") (pin "1") (pinfunction "A_1") (pintype "passive"))
    )
    (net (code "62") (name "Net-(U9-K)") (class "Default")
      (node (ref "P11") (pin "2") (pinfunction "2_2") (pintype "passive"))
      (node (ref "U9") (pin "2") (pinfunction "K_2") (pintype "passive"))
    )
    (net (code "63") (name "unconnected-(J1-SBU1-PadA8)") (class "Default")
      (node (ref "J1") (pin "A8") (pinfunction "SBU1_A8") (pintype "passive+no_connect"))
    )
    (net (code "64") (name "unconnected-(J1-SBU2-PadB8)") (class "Default")
      (node (ref "J1") (pin "B8") (pinfunction "SBU2_B8") (pintype "passive+no_connect"))
    )
    (net (code "65") (name "unconnected-(MD1-IO0-Pad6)") (class "Default")
      (node (ref "MD1") (pin "6") (pinfunction "IO0_6") (pintype "passive"))
    )
    (net (code "66") (name "unconnected-(MD1-IO1-Pad7)") (class "Default")
      (node (ref "MD1") (pin "7") (pinfunction "IO1_7") (pintype "passive"))
    )
    (net (code "67") (name "unconnected-(MD1-IO3-Pad5)") (class "Default")
      (node (ref "MD1") (pin "5") (pinfunction "IO3_5") (pintype "passive"))
    )
    (net (code "68") (name "unconnected-(MD1-IO6-Pad8)") (class "Default")
      (node (ref "MD1") (pin "8") (pinfunction "IO6_8") (pintype "passive"))
    )
    (net (code "69") (name "unconnected-(MD1-NC-Pad20)") (class "Default")
      (node (ref "MD1") (pin "20") (pinfunction "NC_20") (pintype "passive"))
    )
    (net (code "70") (name "unconnected-(MD1-NC-Pad22)") (class "Default")
      (node (ref "MD1") (pin "22") (pinfunction "NC_22") (pintype "passive"))
    )
    (net (code "71") (name "unconnected-(MD1-NC{slash}IO15-Pad19)") (class "Default")
      (node (ref "MD1") (pin "19") (pinfunction "NC/IO15_19") (pintype "passive"))
    )
    (net (code "72") (name "unconnected-(U1-CTS#-Pad5)") (class "Default")
      (node (ref "U1") (pin "5") (pinfunction "CTS#_5") (pintype "passive+no_connect"))
    )
  )
)
